# Maypole_Power.net
KiCad netlist of a schematic drawn in Altium Designer
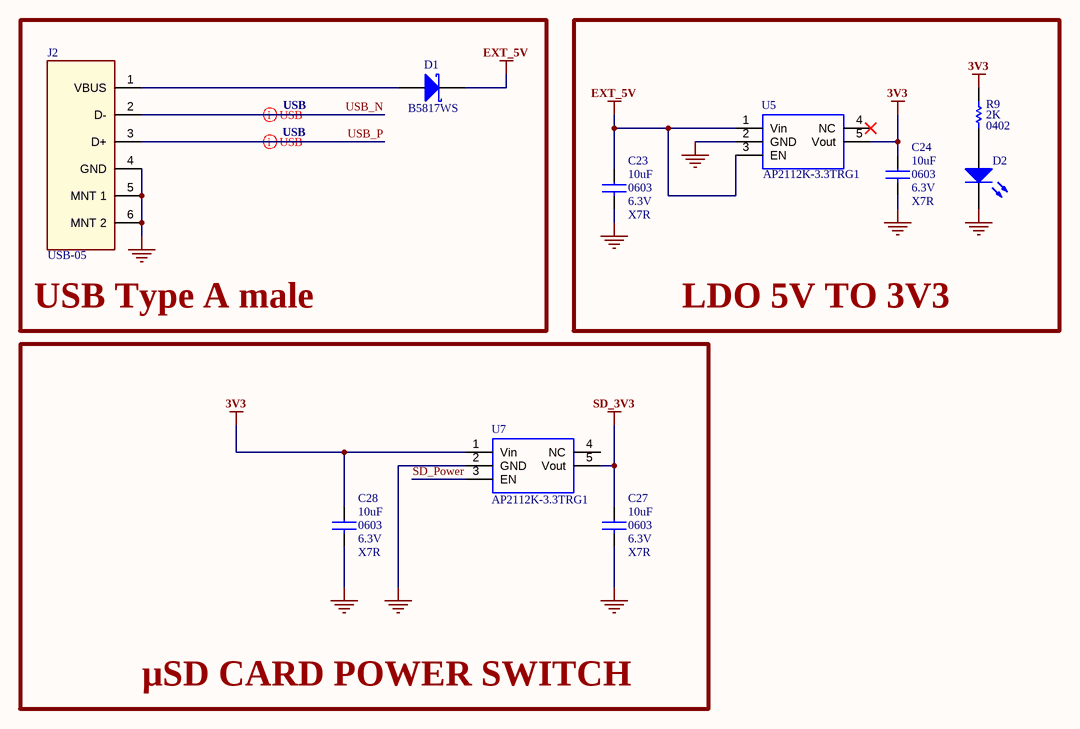
[diagram p0: Maypole Power.SchDoc]

(export (version "E")
  (design (tool "Eeschema 10.0.6"))
  (components
    (comp (ref "C23")
      (value "10uF")
      (footprint "CAPC0603")
      (description "CAP CER 10uF 6.3V X7R 0603")
      (fields
        (field (name "VOLTAGE") "6.3V")
        (field (name "DIELECTRIC") "X7R")
        (field (name "CASE/PACKAGE") "0603")
      )
      (libsource (lib "CUSTOM SCH") (part "Cap"))
    )
    (comp (ref "C24")
      (value "10uF")
      (footprint "CAPC0603")
      (description "CAP CER 10uF 6.3V X7R 0603")
      (fields
        (field (name "VOLTAGE") "6.3V")
        (field (name "DIELECTRIC") "X7R")
        (field (name "CASE/PACKAGE") "0603")
      )
      (libsource (lib "CUSTOM SCH") (part "Cap"))
    )
    (comp (ref "C27")
      (value "10uF")
      (footprint "CAPC0603")
      (description "CAP CER 10uF 6.3V X7R 0603")
      (fields
        (field (name "VOLTAGE") "6.3V")
        (field (name "DIELECTRIC") "X7R")
        (field (name "CASE/PACKAGE") "0603")
      )
      (libsource (lib "CUSTOM SCH") (part "Cap"))
    )
    (comp (ref "C28")
      (value "10uF")
      (footprint "CAPC0603")
      (description "CAP CER 10uF 6.3V X7R 0603")
      (fields
        (field (name "VOLTAGE") "6.3V")
        (field (name "DIELECTRIC") "X7R")
        (field (name "CASE/PACKAGE") "0603")
      )
      (libsource (lib "CUSTOM SCH") (part "Cap"))
    )
    (comp (ref "D1")
      (value "~")
      (footprint "SOD-323")
      (description "20V 1A 450mV @ 1A SOD-323 Schottky Barrier Diodes (SBD) RoHS")
      (fields (field (name "MANUFACTURER PART NUMBER") "B5817WS"))
      (libsource (lib "Pd's Sch Lib") (part "B5817WS"))
    )
    (comp (ref "D2")
      (value "~")
      (footprint "LED_0603")
      (description "LED, RED,SMD, 0603")
      (libsource (lib "Miscellaneous Devices") (part "LED1"))
    )
    (comp (ref "J2")
      (value "~")
      (footprint "Molex_48037-0001_0")
      (description "USB A-type Plug Male PCB R/A")
      (fields (field (name "MANUFACTURER PART NUMBER") "USB-05"))
      (libsource (lib "CUSTOM TNY290PG") (part "USB MALE"))
    )
    (comp (ref "R9")
      (value "2K")
      (footprint "RESC0402")
      (description "Thick Film Resistor -  2Kohm, 1%, 0402")
      (fields (field (name "CASE/PACKAGE") "0402"))
      (libsource (lib "Pd's Sch Lib") (part "Resistor"))
    )
    (comp (ref "U5")
      (value "~")
      (footprint "SOT25")
      (description "LDO Voltage Regulators 600mA CMOS LDO 50mA 3.3V 250mV")
      (fields (field (name "MANUFACTURER PART NUMBER") "AP2112K-3.3TRG1"))
      (libsource (lib "VEGG_Schlib") (part "LDO_5V_3V"))
    )
    (comp (ref "U7")
      (value "~")
      (footprint "SOT25")
      (description "LDO Voltage Regulators 600mA CMOS LDO 50mA 3.3V 250mV")
      (fields (field (name "MANUFACTURER PART NUMBER") "AP2112K-3.3TRG1"))
      (libsource (lib "VEGG_Schlib") (part "LDO_5V_3V"))
    )
  )
  (nets
    (net (code "1") (name "/SD_Power") (class "Default")
      (node (ref "U7") (pin "3") (pinfunction "EN_3") (pintype "passive"))
    )
    (net (code "2") (name "/USB_N") (class "Default")
      (node (ref "J2") (pin "2") (pinfunction "D-_2") (pintype "passive"))
    )
    (net (code "3") (name "/USB_P") (class "Default")
      (node (ref "J2") (pin "3") (pinfunction "D+_3") (pintype "passive"))
    )
    (net (code "4") (name "3V3") (class "Default")
      (node (ref "C24") (pin "1") (pinfunction "1_1") (pintype "passive"))
      (node (ref "C28") (pin "1") (pinfunction "1_1") (pintype "passive"))
      (node (ref "R9") (pin "1") (pinfunction "1_1") (pintype "passive"))
      (node (ref "U5") (pin "5") (pinfunction "Vout_5") (pintype "power_in"))
      (node (ref "U7") (pin "1") (pinfunction "Vin_1") (pintype "power_in"))
    )
    (net (code "5") (name "EXT_5V") (class "Default")
      (node (ref "C23") (pin "1") (pinfunction "1_1") (pintype "passive"))
      (node (ref "D1") (pin "K") (pinfunction "K_K") (pintype "passive"))
      (node (ref "U5") (pin "1") (pinfunction "Vin_1") (pintype "power_in"))
      (node (ref "U5") (pin "3") (pinfunction "EN_3") (pintype "passive"))
    )
    (net (code "6") (name "GND") (class "Default")
      (node (ref "C23") (pin "2") (pinfunction "2_2") (pintype "passive"))
      (node (ref "C24") (pin "2") (pinfunction "2_2") (pintype "passive"))
      (node (ref "C27") (pin "2") (pinfunction "2_2") (pintype "passive"))
      (node (ref "C28") (pin "2") (pinfunction "2_2") (pintype "passive"))
      (node (ref "D2") (pin "K") (pinfunction "K_K") (pintype "passive"))
      (node (ref "J2") (pin "4") (pinfunction "GND_4") (pintype "passive"))
      (node (ref "J2") (pin "5") (pinfunction "MNT_1_5") (pintype "passive"))
      (node (ref "J2") (pin "6") (pinfunction "MNT_2_6") (pintype "passive"))
      (node (ref "U5") (pin "2") (pinfunction "GND_2") (pintype "power_in"))
      (node (ref "U7") (pin "2") (pinfunction "GND_2") (pintype "power_in"))
    )
    (net (code "7") (name "Net-(D2-PadA)") (class "Default")
      (node (ref "D2") (pin "A") (pinfunction "A_A") (pintype "passive"))
      (node (ref "R9") (pin "2") (pinfunction "2_2") (pintype "passive"))
    )
    (net (code "8") (name "Net-(J2-VBUS)") (class "Default")
      (node (ref "D1") (pin "A") (pinfunction "A_A") (pintype "passive"))
      (node (ref "J2") (pin "1") (pinfunction "VBUS_1") (pintype "passive"))
    )
    (net (code "9") (name "SD_3V3") (class "Default")
      (node (ref "C27") (pin "1") (pinfunction "1_1") (pintype "passive"))
      (node (ref "U7") (pin "5") (pinfunction "Vout_5") (pintype "power_in"))
    )
    (net (code "10") (name "unconnected-(U5-NC-Pad4)") (class "Default")
      (node (ref "U5") (pin "4") (pinfunction "NC_4") (pintype "passive+no_connect"))
    )
    (net (code "11") (name "unconnected-(U7-NC-Pad4)") (class "Default")
      (node (ref "U7") (pin "4") (pinfunction "NC_4") (pintype "passive"))
    )
  )
)
